# attiniest85-display-shield-mk-1_1.net
KiCad netlist of a schematic drawn in EAGLE
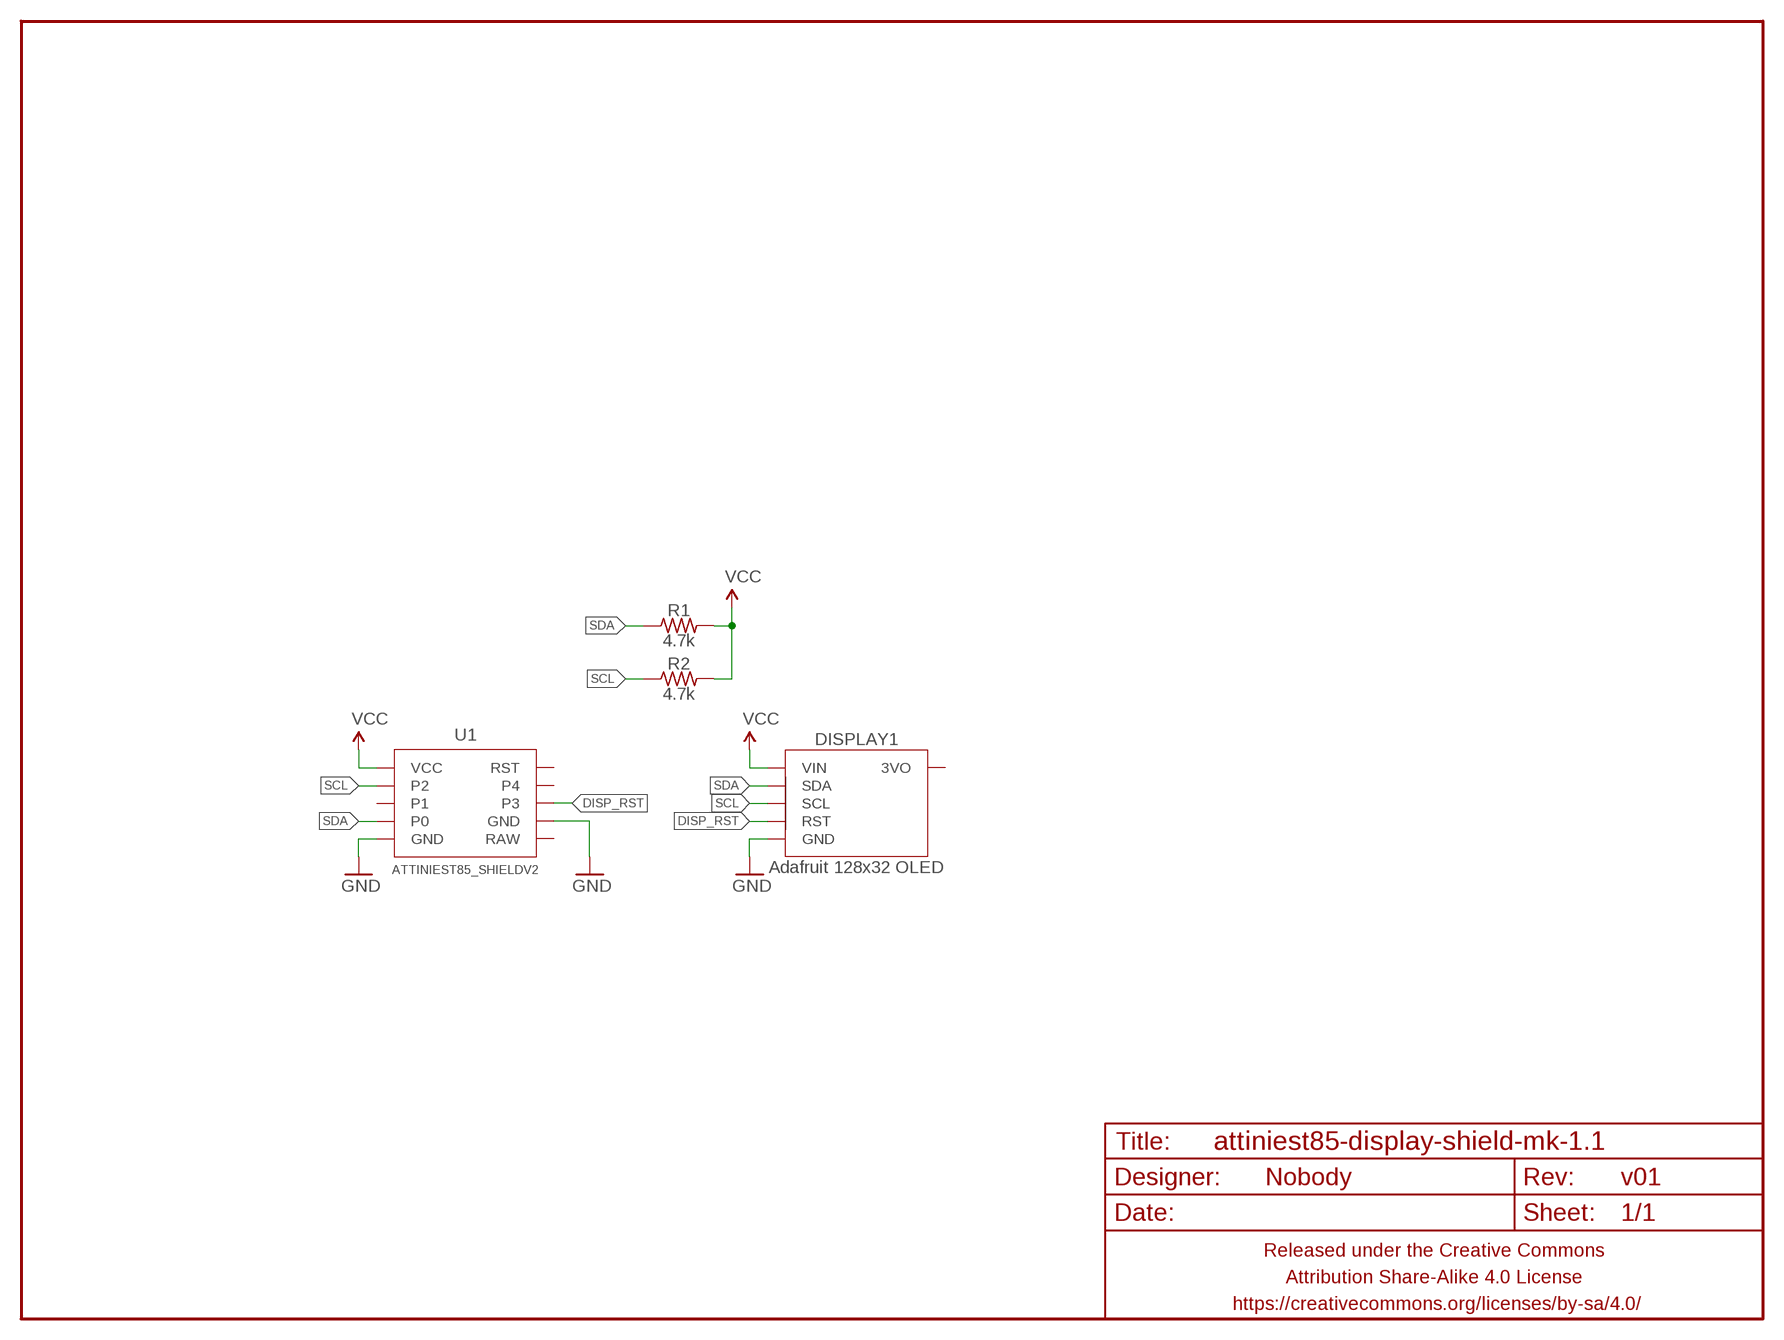
[diagram p0: schematic, sheet 1]

(export (version "E")
  (design (tool "Eeschema 10.0.6"))
  (components
    (comp (ref "DISPLAY1")
      (value "Adafruit 128x32 OLED")
      (footprint "eagle-import:ADAFRUIT_128X32_OLED_I2C_CLOSER_NOHOLES")
      (libsource (lib "eagle-import") (part "ADAFRUIT_128X32_OLED_I2CNOHOLES"))
    )
    (comp (ref "FRAME1")
      (value "FRAME-LETTERNO_PACKAGE")
      (footprint "eagle-import:DUMMY")
      (fields (field (name "DESIGNER") "Nobody"))
      (libsource (lib "eagle-import") (part "FRAME-LETTERNO_PACKAGE"))
    )
    (comp (ref "R1")
      (value "4.7k")
      (footprint "eagle-import:RESISTOR-AXIAL-PTH-7.62MM")
      (libsource (lib "eagle-import") (part "RESISTORPTH-AXIAL-7.62MM"))
    )
    (comp (ref "R2")
      (value "4.7k")
      (footprint "eagle-import:RESISTOR-AXIAL-PTH-7.62MM")
      (libsource (lib "eagle-import") (part "RESISTORPTH-AXIAL-7.62MM"))
    )
    (comp (ref "U1")
      (value "ATTINIEST85_SHIELDV2")
      (footprint "eagle-import:ATTINIEST85_SHIELD_V2")
      (libsource (lib "eagle-import") (part "ATTINIEST85_SHIELDV2"))
    )
  )
  (nets
    (net (code "1") (name "DISP_RST") (class "Default")
      (node (ref "DISPLAY1") (pin "RST") (pinfunction "RST_RST") (pintype "bidirectional"))
      (node (ref "U1") (pin "3") (pinfunction "P3_3") (pintype "bidirectional"))
    )
    (net (code "2") (name "GND") (class "Default")
      (node (ref "DISPLAY1") (pin "GND") (pinfunction "GND_GND") (pintype "bidirectional"))
      (node (ref "U1") (pin "GND@1") (pinfunction "GND_GND@1") (pintype "bidirectional"))
      (node (ref "U1") (pin "GND@2") (pinfunction "GND_GND@2") (pintype "bidirectional"))
    )
    (net (code "3") (name "SCL") (class "Default")
      (node (ref "DISPLAY1") (pin "SCL") (pinfunction "SCL_SCL") (pintype "bidirectional"))
      (node (ref "R2") (pin "P$1") (pinfunction "1_P$1") (pintype "passive"))
      (node (ref "U1") (pin "2") (pinfunction "P2_2") (pintype "bidirectional"))
    )
    (net (code "4") (name "SDA") (class "Default")
      (node (ref "DISPLAY1") (pin "SDA") (pinfunction "SDA_SDA") (pintype "bidirectional"))
      (node (ref "R1") (pin "P$1") (pinfunction "1_P$1") (pintype "passive"))
      (node (ref "U1") (pin "0") (pinfunction "P0_0") (pintype "bidirectional"))
    )
    (net (code "5") (name "VCC") (class "Default")
      (node (ref "DISPLAY1") (pin "VIN") (pinfunction "VIN_VIN") (pintype "bidirectional"))
      (node (ref "R1") (pin "P$2") (pinfunction "2_P$2") (pintype "passive"))
      (node (ref "R2") (pin "P$2") (pinfunction "2_P$2") (pintype "passive"))
      (node (ref "U1") (pin "VCC") (pinfunction "VCC_VCC") (pintype "bidirectional"))
    )
    (net (code "6") (name "unconnected-(DISPLAY1-Pad3VO)") (class "Default")
      (node (ref "DISPLAY1") (pin "3VO") (pinfunction "3VO_3VO") (pintype "bidirectional"))
    )
    (net (code "7") (name "unconnected-(U1-P1-Pad1)") (class "Default")
      (node (ref "U1") (pin "1") (pinfunction "P1_1") (pintype "bidirectional"))
    )
    (net (code "8") (name "unconnected-(U1-P4-Pad4)") (class "Default")
      (node (ref "U1") (pin "4") (pinfunction "P4_4") (pintype "bidirectional"))
    )
    (net (code "9") (name "unconnected-(U1-PadRAW)") (class "Default")
      (node (ref "U1") (pin "RAW") (pinfunction "RAW_RAW") (pintype "bidirectional"))
    )
    (net (code "10") (name "unconnected-(U1-PadRST)") (class "Default")
      (node (ref "U1") (pin "RST") (pinfunction "RST_RST") (pintype "bidirectional"))
    )
  )
)
